# POWER_Management.net
KiCad netlist of a schematic drawn in Altium Designer
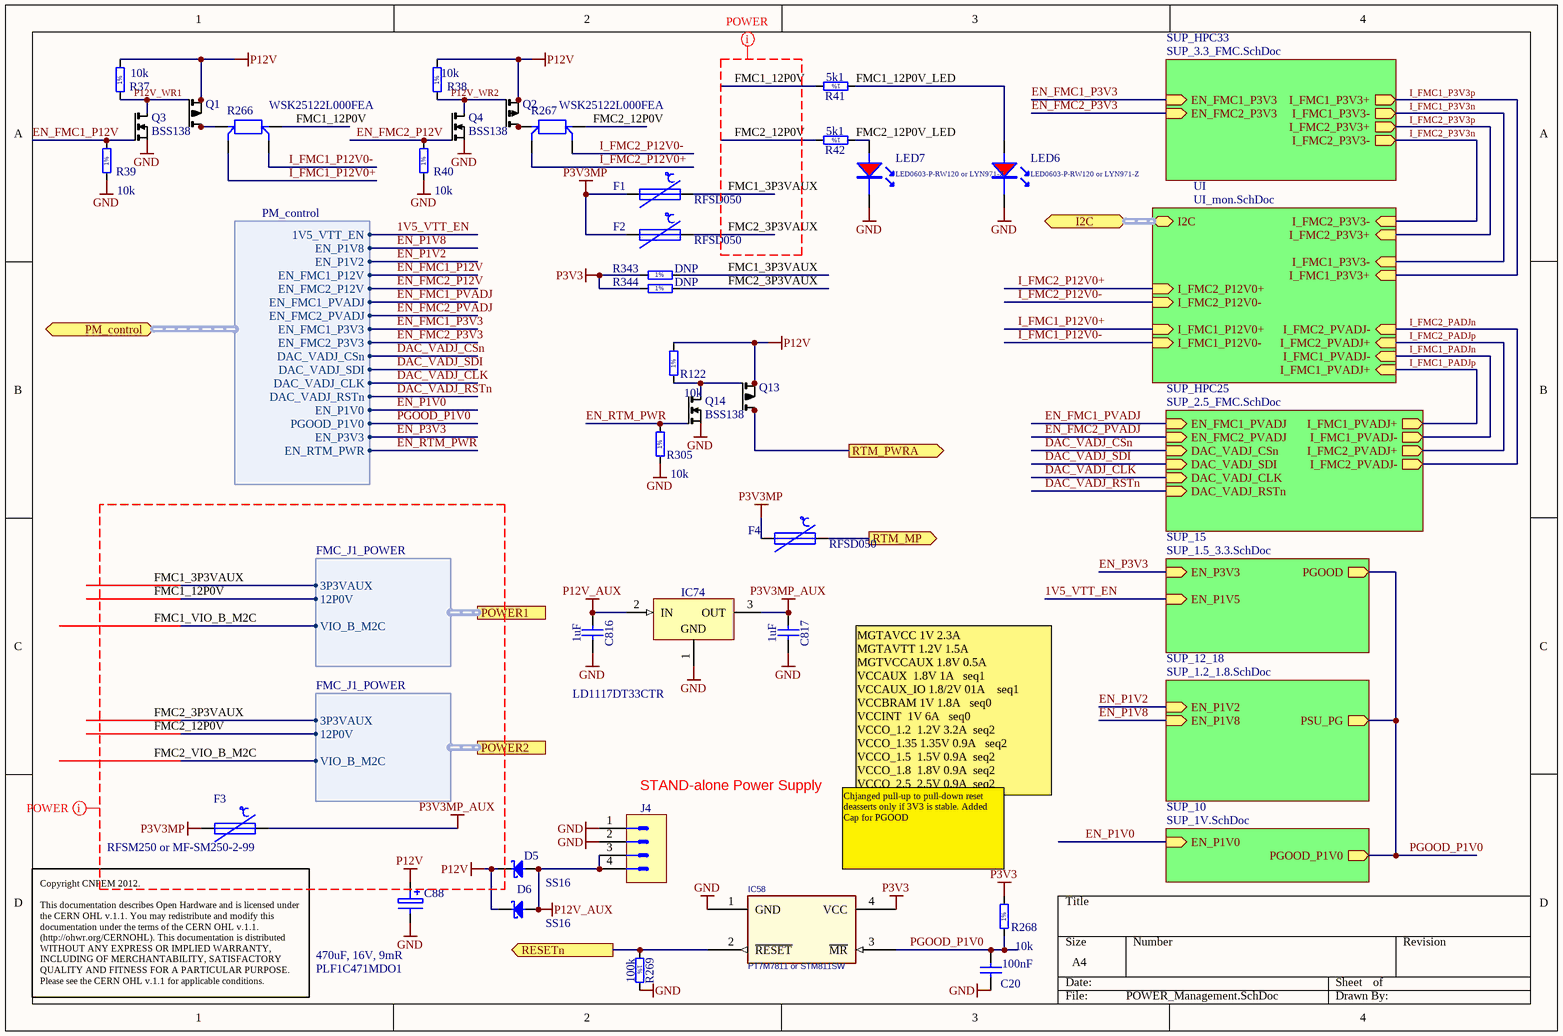
[diagram p0: POWER_Management.SchDoc]

(export (version "E")
  (design (tool "Eeschema 10.0.6"))
  (components
    (comp (ref "C20")
      (value "100nF")
      (footprint "CAPC0603X33N")
      (description "Non-polarised capacitor")
      (fields
        (field (name "PART NUMBER") "CC0201_100NF_6.3V_10%_X5R")
        (field (name "VOLTAGE") "6.3V")
        (field (name "AUTHOR") "CERN DEM JLC")
      )
      (libsource (lib "Capacitors") (part "Capacitor - non polarized"))
    )
    (comp (ref "C88")
      (value "PLF1C471MDO1")
      (footprint "CAPPR500-1000X1250")
      (description "POLY, 470uF, 16V, ESR: 9mR")
      (fields (field (name "ALTIUM_VALUE") "470uF, 16V, 9mR"))
      (libsource (lib "LIBRARY_SCH") (part "CAP_POLYMER_10mm"))
    )
    (comp (ref "C816")
      (value "1uF")
      (footprint "CAPC1608X87N")
      (description "Non-polarised capacitor")
      (fields
        (field (name "PART NUMBER") "CC0603_1UF_16V_10%_X7R")
        (field (name "VOLTAGE") "16V")
        (field (name "AUTHOR") "CERN DEM JLC")
      )
      (libsource (lib "Capacitors") (part "Capacitor - non polarized"))
    )
    (comp (ref "C817")
      (value "1uF")
      (footprint "CAPC1608X87N")
      (description "Non-polarised capacitor")
      (fields
        (field (name "PART NUMBER") "CC0603_1UF_16V_10%_X7R")
        (field (name "VOLTAGE") "16V")
        (field (name "AUTHOR") "CERN DEM JLC")
      )
      (libsource (lib "Capacitors") (part "Capacitor - non polarized"))
    )
    (comp (ref "D5")
      (value "SS16")
      (footprint "DIOM5127X229N")
      (description "Schottky Diode")
      (fields
        (field (name "VOLTAGE") "60V")
        (field (name "POWER") "1A")
        (field (name "AUTHOR") "CERN DEM JLC")
      )
      (libsource (lib "ICs And Semiconductors") (part "Diode Schottky"))
    )
    (comp (ref "D6")
      (value "SS16")
      (footprint "DIOM5127X229N")
      (description "Schottky Diode")
      (fields
        (field (name "VOLTAGE") "60V")
        (field (name "POWER") "1A")
        (field (name "AUTHOR") "CERN DEM JLC")
      )
      (libsource (lib "ICs And Semiconductors") (part "Diode Schottky"))
    )
    (comp (ref "F1")
      (value "RFSD050")
      (footprint "PTC_SMD_1812")
      (description "0.50A/15V")
      (libsource (lib "LIBRARY_SCH") (part "F_PTC_1812"))
    )
    (comp (ref "F2")
      (value "RFSD050")
      (footprint "PTC_SMD_1812")
      (description "0.50A/15V")
      (libsource (lib "LIBRARY_SCH") (part "F_PTC_1812"))
    )
    (comp (ref "F3")
      (value "RFSM250 or MF-SM250-2-99")
      (footprint "SMD150-2")
      (description "2.50A/15V")
      (libsource (lib "LIBRARY_SCH") (part "F_PTC_9.5x6mm"))
    )
    (comp (ref "F4")
      (value "RFSD050")
      (footprint "PTC_SMD_1812")
      (description "0.50A/15V")
      (libsource (lib "LIBRARY_SCH") (part "F_PTC_1812"))
    )
    (comp (ref "IC58")
      (value "PT7M7811 or STM811SW")
      (footprint "SOT143B")
      (description "voltage supervisor")
      (libsource (lib "LIBRARY_SCH") (part "VOLT_STM811"))
    )
    (comp (ref "IC74")
      (value "LD1117DT33CTR")
      (footprint "TO228P972X240-3N-R540X510")
      (description "3-Terminal Regulator 1=GND 2=IN 3=OUT")
      (fields (field (name "MANUFACTURER") "ST MICROELECTRONICS") (field (name "AUTHOR") "CERN DEM JLC"))
      (libsource (lib "ICs And Semiconductors") (part "REG3 1GND-2IN-3OUT"))
    )
    (comp (ref "J4")
      (value "Mini-Fit Jr.™")
      (footprint "MOLEX_39-28-1043")
      (description "Connector 4 Male")
      (fields
        (field (name "PART NUMBER") "MOLEX_39-28-1043")
        (field (name "MANUFACTURER") "MOLEX")
        (field (name "AUTHOR") "CERN DEM JLC")
      )
      (libsource (lib "Connectors") (part "Connector 4 Male"))
    )
    (comp (ref "LED6")
      (value "LED0603-P-RW120 or LYN971-Z")
      (footprint "led_0603R")
      (description "LED 0603 red")
      (libsource (lib "LIBRARY_SCH") (part "LED_0603R"))
    )
    (comp (ref "LED7")
      (value "LED0603-P-RW120 or LYN971-Z")
      (footprint "led_0603R")
      (description "LED 0603 red")
      (libsource (lib "LIBRARY_SCH") (part "LED_0603R"))
    )
    (comp (ref "Q1")
      (value "IRF9317PBF  or IRF9310PbF")
      (footprint "so-8")
      (description "PMOS 30V, 4.6mR, 20A, 2.5W")
      (libsource (lib "LIBRARY_SCH") (part "Q_IRF9310"))
    )
    (comp (ref "Q2")
      (value "IRF9317PBF  or IRF9310PbF")
      (footprint "so-8")
      (description "PMOS 30V, 4.6mR, 20A, 2.5W")
      (libsource (lib "LIBRARY_SCH") (part "Q_IRF9310"))
    )
    (comp (ref "Q3")
      (value "BSS138")
      (footprint "SOT95P251X112-3N")
      (libsource (lib "LIBRARY_SCH") (part "Q_BSS138"))
    )
    (comp (ref "Q4")
      (value "BSS138")
      (footprint "SOT95P251X112-3N")
      (libsource (lib "LIBRARY_SCH") (part "Q_BSS138"))
    )
    (comp (ref "Q13")
      (value "IRF9317PBF  or IRF9310PbF")
      (footprint "so-8")
      (description "PMOS 30V, 4.6mR, 20A, 2.5W")
      (libsource (lib "LIBRARY_SCH") (part "Q_IRF9310"))
    )
    (comp (ref "Q14")
      (value "BSS138")
      (footprint "SOT95P251X112-3N")
      (libsource (lib "LIBRARY_SCH") (part "Q_BSS138"))
    )
    (comp (ref "R37")
      (value "10k")
      (footprint "RESC1005X40N")
      (description "Resistor - 1%")
      (fields
        (field (name "PART NUMBER") "R0402_10K_1%_0.0625W_100PPM")
        (field (name "POWER") "0.0625W")
        (field (name "AUTHOR") "CERN DEM JLC")
      )
      (libsource (lib "Resistors") (part "Resistor - 1%"))
    )
    (comp (ref "R38")
      (value "10k")
      (footprint "RESC1005X40N")
      (description "Resistor - 1%")
      (fields
        (field (name "PART NUMBER") "R0402_10K_1%_0.0625W_100PPM")
        (field (name "POWER") "0.0625W")
        (field (name "AUTHOR") "CERN DEM JLC")
      )
      (libsource (lib "Resistors") (part "Resistor - 1%"))
    )
    (comp (ref "R39")
      (value "10k")
      (footprint "RESC1005X40N")
      (description "Resistor - 1%")
      (fields
        (field (name "PART NUMBER") "R0402_10K_1%_0.0625W_100PPM")
        (field (name "POWER") "0.0625W")
        (field (name "AUTHOR") "CERN DEM JLC")
      )
      (libsource (lib "Resistors") (part "Resistor - 1%"))
    )
    (comp (ref "R40")
      (value "10k")
      (footprint "RESC1005X40N")
      (description "Resistor - 1%")
      (fields
        (field (name "PART NUMBER") "R0402_10K_1%_0.0625W_100PPM")
        (field (name "POWER") "0.0625W")
        (field (name "AUTHOR") "CERN DEM JLC")
      )
      (libsource (lib "Resistors") (part "Resistor - 1%"))
    )
    (comp (ref "R41")
      (value "5k1")
      (footprint "RESC1608X55N")
      (description "Resistor - 1%")
      (fields
        (field (name "PART NUMBER") "R0603_5K1_1%_0.1W_100PPM")
        (field (name "POWER") "0.1W")
        (field (name "AUTHOR") "CERN DEM JLC")
      )
      (libsource (lib "Resistors") (part "Resistor - 1%"))
    )
    (comp (ref "R42")
      (value "5k1")
      (footprint "RESC1608X55N")
      (description "Resistor - 1%")
      (fields
        (field (name "PART NUMBER") "R0603_5K1_1%_0.1W_100PPM")
        (field (name "POWER") "0.1W")
        (field (name "AUTHOR") "CERN DEM JLC")
      )
      (libsource (lib "Resistors") (part "Resistor - 1%"))
    )
    (comp (ref "R122")
      (value "10k")
      (footprint "RESC1005X40N")
      (description "Resistor - 1%")
      (fields
        (field (name "PART NUMBER") "R0402_10K_1%_0.0625W_100PPM")
        (field (name "POWER") "0.0625W")
        (field (name "AUTHOR") "CERN DEM JLC")
      )
      (libsource (lib "Resistors") (part "Resistor - 1%"))
    )
    (comp (ref "R266")
      (value "WSK25122L000FEA")
      (footprint "RES_WSK2512")
      (description "RESISTOR, METAL STRIP, 0.001 OHM 1%")
      (libsource (lib "LIBRARY_SCH") (part "RES_POW_Kelvin"))
    )
    (comp (ref "R267")
      (value "WSK25122L000FEA")
      (footprint "RES_WSK2512")
      (description "RESISTOR, METAL STRIP, 0.001 OHM 1%")
      (libsource (lib "LIBRARY_SCH") (part "RES_POW_Kelvin"))
    )
    (comp (ref "R268")
      (value "10k")
      (footprint "RESC1005X40N")
      (description "Resistor - 1%")
      (fields
        (field (name "PART NUMBER") "R0402_10K_1%_0.0625W_100PPM")
        (field (name "POWER") "0.0625W")
        (field (name "AUTHOR") "CERN DEM JLC")
      )
      (libsource (lib "Resistors") (part "Resistor - 1%"))
    )
    (comp (ref "R269")
      (value "100k")
      (footprint "RESC1005X40N")
      (description "Resistor - 1%")
      (fields
        (field (name "PART NUMBER") "R0402_100K_1%_0.0625W_100PPM")
        (field (name "POWER") "0.0625W")
        (field (name "AUTHOR") "CERN DEM JLC")
      )
      (libsource (lib "Resistors") (part "Resistor - 1%"))
    )
    (comp (ref "R305")
      (value "10k")
      (footprint "RESC1005X40N")
      (description "Resistor - 1%")
      (fields
        (field (name "PART NUMBER") "R0402_10K_1%_0.0625W_100PPM")
        (field (name "POWER") "0.0625W")
        (field (name "AUTHOR") "CERN DEM JLC")
      )
      (libsource (lib "Resistors") (part "Resistor - 1%"))
    )
    (comp (ref "R343")
      (value "DNP")
      (footprint "RESC1005X40N")
      (description "Resistor - 1%")
      (fields
        (field (name "PART NUMBER") "R0402_0R_JUMPER")
        (field (name "MANUFACTURER") "GENERIC")
        (field (name "AUTHOR") "CERN DEM JLC")
      )
      (libsource (lib "Resistors") (part "Resistor - 1%"))
    )
    (comp (ref "R344")
      (value "DNP")
      (footprint "RESC1005X40N")
      (description "Resistor - 1%")
      (fields
        (field (name "PART NUMBER") "R0402_0R_JUMPER")
        (field (name "MANUFACTURER") "GENERIC")
        (field (name "AUTHOR") "CERN DEM JLC")
      )
      (libsource (lib "Resistors") (part "Resistor - 1%"))
    )
  )
  (nets
    (net (code "10") (name "/EN_FMC1_P12V") (class "Default")
      (node (ref "Q3") (pin "1") (pinfunction "G_1") (pintype "input"))
      (node (ref "R39") (pin "2") (pinfunction "2_2") (pintype "passive"))
    )
    (net (code "13") (name "/EN_FMC2_P12V") (class "Default")
      (node (ref "Q4") (pin "1") (pinfunction "G_1") (pintype "input"))
      (node (ref "R40") (pin "2") (pinfunction "2_2") (pintype "passive"))
    )
    (net (code "19") (name "/EN_RTM_PWR") (class "Default")
      (node (ref "Q14") (pin "1") (pinfunction "G_1") (pintype "input"))
      (node (ref "R305") (pin "2") (pinfunction "2_2") (pintype "passive"))
    )
    (net (code "20") (name "/FMC1_3P3VAUX") (class "Default")
      (node (ref "F1") (pin "2") (pinfunction "2_2") (pintype "passive"))
      (node (ref "R343") (pin "2") (pinfunction "2_2") (pintype "passive"))
    )
    (net (code "21") (name "/FMC1_12P0V") (class "Default")
      (node (ref "R266") (pin "2") (pinfunction "2_2") (pintype "passive"))
      (node (ref "R41") (pin "2") (pinfunction "2_2") (pintype "passive"))
    )
    (net (code "22") (name "/FMC1_12P0V_LED") (class "Default")
      (node (ref "LED6") (pin "A") (pinfunction "A_A") (pintype "passive"))
      (node (ref "R41") (pin "1") (pinfunction "1_1") (pintype "passive"))
    )
    (net (code "24") (name "/FMC2_3P3VAUX") (class "Default")
      (node (ref "F2") (pin "2") (pinfunction "2_2") (pintype "passive"))
      (node (ref "R344") (pin "2") (pinfunction "2_2") (pintype "passive"))
    )
    (net (code "25") (name "/FMC2_12P0V") (class "Default")
      (node (ref "R267") (pin "2") (pinfunction "2_2") (pintype "passive"))
      (node (ref "R42") (pin "2") (pinfunction "2_2") (pintype "passive"))
    )
    (net (code "26") (name "/FMC2_12P0V_LED") (class "Default")
      (node (ref "LED7") (pin "A") (pinfunction "A_A") (pintype "passive"))
      (node (ref "R42") (pin "1") (pinfunction "1_1") (pintype "passive"))
    )
    (net (code "31") (name "/I_FMC1_P12V0+") (class "Default")
      (node (ref "R266") (pin "1a") (pinfunction "1a_1a") (pintype "passive"))
    )
    (net (code "32") (name "/I_FMC1_P12V0-") (class "Default")
      (node (ref "R266") (pin "2a") (pinfunction "2a_2a") (pintype "passive"))
    )
    (net (code "37") (name "/I_FMC2_P12V0+") (class "Default")
      (node (ref "R267") (pin "1a") (pinfunction "1a_1a") (pintype "passive"))
    )
    (net (code "38") (name "/I_FMC2_P12V0-") (class "Default")
      (node (ref "R267") (pin "2a") (pinfunction "2a_2a") (pintype "passive"))
    )
    (net (code "41") (name "/P12V_WR1") (class "Default")
      (node (ref "Q1") (pin "4") (pinfunction "G1_4") (pintype "input"))
      (node (ref "Q3") (pin "3") (pinfunction "D_3") (pintype "passive"))
      (node (ref "R37") (pin "1") (pinfunction "1_1") (pintype "passive"))
    )
    (net (code "42") (name "/P12V_WR2") (class "Default")
      (node (ref "Q2") (pin "4") (pinfunction "G1_4") (pintype "input"))
      (node (ref "Q4") (pin "3") (pinfunction "D_3") (pintype "passive"))
      (node (ref "R38") (pin "1") (pinfunction "1_1") (pintype "passive"))
    )
    (net (code "43") (name "/PGOOD_P1V0") (class "Default")
      (node (ref "C20") (pin "1") (pinfunction "1_1") (pintype "passive"))
      (node (ref "IC58") (pin "3") (pinfunction "~{MR}_3") (pintype "input"))
      (node (ref "R268") (pin "1") (pinfunction "1_1") (pintype "passive"))
    )
    (net (code "44") (name "/RESETn") (class "Default")
      (node (ref "IC58") (pin "2") (pinfunction "~{RESET}_2") (pintype "output"))
      (node (ref "R269") (pin "1") (pinfunction "1_1") (pintype "passive"))
    )
    (net (code "45") (name "/RTM_MP") (class "Default")
      (node (ref "F4") (pin "2") (pinfunction "2_2") (pintype "passive"))
    )
    (net (code "46") (name "/RTM_PWRA") (class "Default")
      (node (ref "Q13") (pin "5") (pinfunction "D1_5") (pintype "open_collector"))
      (node (ref "Q13") (pin "6") (pinfunction "D1_6") (pintype "open_collector"))
      (node (ref "Q13") (pin "7") (pinfunction "D1_7") (pintype "open_collector"))
      (node (ref "Q13") (pin "8") (pinfunction "D1_8") (pintype "open_collector"))
    )
    (net (code "49") (name "GND") (class "Default")
      (node (ref "C20") (pin "2") (pinfunction "2_2") (pintype "passive"))
      (node (ref "C816") (pin "2") (pinfunction "2_2") (pintype "passive"))
      (node (ref "C817") (pin "2") (pinfunction "2_2") (pintype "passive"))
      (node (ref "C88") (pin "2") (pinfunction "2_2") (pintype "passive"))
      (node (ref "IC58") (pin "1") (pinfunction "GND_1") (pintype "power_in"))
      (node (ref "IC74") (pin "1") (pinfunction "GND_1") (pintype "power_in"))
      (node (ref "J4") (pin "1") (pinfunction "1_1") (pintype "passive"))
      (node (ref "J4") (pin "2") (pinfunction "2_2") (pintype "passive"))
      (node (ref "LED6") (pin "K") (pinfunction "K_K") (pintype "passive"))
      (node (ref "LED7") (pin "K") (pinfunction "K_K") (pintype "passive"))
      (node (ref "Q14") (pin "2") (pinfunction "S_2") (pintype "passive"))
      (node (ref "Q3") (pin "2") (pinfunction "S_2") (pintype "passive"))
      (node (ref "Q4") (pin "2") (pinfunction "S_2") (pintype "passive"))
      (node (ref "R269") (pin "2") (pinfunction "2_2") (pintype "passive"))
      (node (ref "R305") (pin "1") (pinfunction "1_1") (pintype "passive"))
      (node (ref "R39") (pin "1") (pinfunction "1_1") (pintype "passive"))
      (node (ref "R40") (pin "1") (pinfunction "1_1") (pintype "passive"))
    )
    (net (code "50") (name "Net-(Q1-D1-Pad5)") (class "Default")
      (node (ref "Q1") (pin "5") (pinfunction "D1_5") (pintype "open_collector"))
      (node (ref "Q1") (pin "6") (pinfunction "D1_6") (pintype "open_collector"))
      (node (ref "Q1") (pin "7") (pinfunction "D1_7") (pintype "open_collector"))
      (node (ref "Q1") (pin "8") (pinfunction "D1_8") (pintype "open_collector"))
      (node (ref "R266") (pin "1") (pinfunction "1_1") (pintype "passive"))
    )
    (net (code "51") (name "Net-(Q2-D1-Pad5)") (class "Default")
      (node (ref "Q2") (pin "5") (pinfunction "D1_5") (pintype "open_collector"))
      (node (ref "Q2") (pin "6") (pinfunction "D1_6") (pintype "open_collector"))
      (node (ref "Q2") (pin "7") (pinfunction "D1_7") (pintype "open_collector"))
      (node (ref "Q2") (pin "8") (pinfunction "D1_8") (pintype "open_collector"))
      (node (ref "R267") (pin "1") (pinfunction "1_1") (pintype "passive"))
    )
    (net (code "52") (name "Net-(Q13-G1)") (class "Default")
      (node (ref "Q13") (pin "4") (pinfunction "G1_4") (pintype "input"))
      (node (ref "Q14") (pin "3") (pinfunction "D_3") (pintype "passive"))
      (node (ref "R122") (pin "1") (pinfunction "1_1") (pintype "passive"))
    )
    (net (code "53") (name "P3V3") (class "Default")
      (node (ref "IC58") (pin "4") (pinfunction "VCC_4") (pintype "power_in"))
      (node (ref "R268") (pin "2") (pinfunction "2_2") (pintype "passive"))
      (node (ref "R343") (pin "1") (pinfunction "1_1") (pintype "passive"))
      (node (ref "R344") (pin "1") (pinfunction "1_1") (pintype "passive"))
    )
    (net (code "54") (name "P3V3MP") (class "Default")
      (node (ref "F1") (pin "1") (pinfunction "1_1") (pintype "passive"))
      (node (ref "F2") (pin "1") (pinfunction "1_1") (pintype "passive"))
      (node (ref "F3") (pin "1") (pinfunction "1_1") (pintype "passive"))
      (node (ref "F4") (pin "1") (pinfunction "1_1") (pintype "passive"))
    )
    (net (code "55") (name "P3V3MP_AUX") (class "Default")
      (node (ref "C817") (pin "1") (pinfunction "1_1") (pintype "passive"))
      (node (ref "F3") (pin "2") (pinfunction "2_2") (pintype "passive"))
      (node (ref "IC74") (pin "3") (pinfunction "OUT_3") (pintype "power_in"))
    )
    (net (code "56") (name "P12V") (class "Default")
      (node (ref "C88") (pin "1") (pinfunction "1_1") (pintype "passive"))
      (node (ref "D5") (pin "1") (pinfunction "C_1") (pintype "passive"))
      (node (ref "D6") (pin "1") (pinfunction "C_1") (pintype "passive"))
      (node (ref "Q1") (pin "1") (pinfunction "S1_1") (pintype "open_emitter"))
      (node (ref "Q1") (pin "2") (pinfunction "S1_2") (pintype "open_emitter"))
      (node (ref "Q1") (pin "3") (pinfunction "S1_3") (pintype "open_emitter"))
      (node (ref "Q13") (pin "1") (pinfunction "S1_1") (pintype "open_emitter"))
      (node (ref "Q13") (pin "2") (pinfunction "S1_2") (pintype "open_emitter"))
      (node (ref "Q13") (pin "3") (pinfunction "S1_3") (pintype "open_emitter"))
      (node (ref "Q2") (pin "1") (pinfunction "S1_1") (pintype "open_emitter"))
      (node (ref "Q2") (pin "2") (pinfunction "S1_2") (pintype "open_emitter"))
      (node (ref "Q2") (pin "3") (pinfunction "S1_3") (pintype "open_emitter"))
      (node (ref "R122") (pin "2") (pinfunction "2_2") (pintype "passive"))
      (node (ref "R37") (pin "2") (pinfunction "2_2") (pintype "passive"))
      (node (ref "R38") (pin "2") (pinfunction "2_2") (pintype "passive"))
    )
    (net (code "57") (name "P12V_AUX") (class "Default")
      (node (ref "C816") (pin "1") (pinfunction "1_1") (pintype "passive"))
      (node (ref "D5") (pin "2") (pinfunction "A_2") (pintype "passive"))
      (node (ref "D6") (pin "2") (pinfunction "A_2") (pintype "passive"))
      (node (ref "IC74") (pin "2") (pinfunction "IN_2") (pintype "input"))
      (node (ref "J4") (pin "3") (pinfunction "3_3") (pintype "passive"))
      (node (ref "J4") (pin "4") (pinfunction "4_4") (pintype "passive"))
    )
  )
)
